# Port_Deployable_Headers.net
KiCad netlist of a schematic drawn in Altium Designer
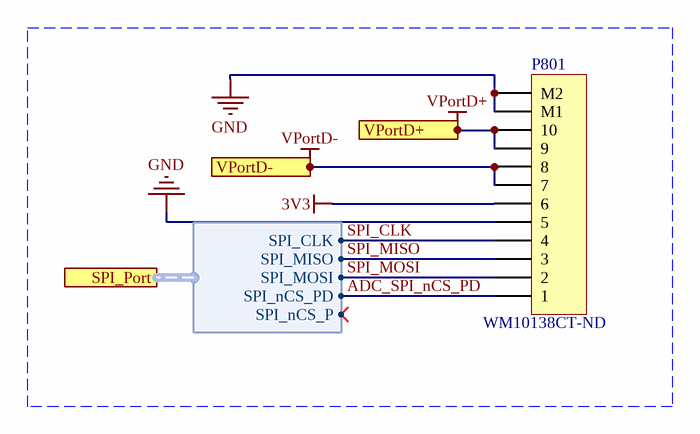
[diagram p0: Port_Deployable_Headers.SchDoc]

(export (version "E")
  (design (tool "Eeschema 10.0.6"))
  (components
    (comp (ref "P801")
      (value "WM10138CT-ND")
      (footprint "MOLX-5040501091")
      (description "CONN HEADER SMD R/A 10POS 1.5MM")
      (fields
        (field (name "PART NUMBER") "69")
        (field (name "MANUFACTURER PART NUMBER") "5040501091")
        (field (name "PUBLISHER") "Altium Limited")
      )
      (libsource (lib "Database") (part "Header 12"))
    )
  )
  (nets
    (net (code "2") (name "/ADC_SPI_nCS_PD") (class "Default")
      (node (ref "P801") (pin "1") (pinfunction "1_1") (pintype "passive"))
    )
    (net (code "3") (name "/SPI_CLK") (class "Default")
      (node (ref "P801") (pin "4") (pinfunction "4_4") (pintype "passive"))
    )
    (net (code "4") (name "/SPI_MISO") (class "Default")
      (node (ref "P801") (pin "3") (pinfunction "3_3") (pintype "passive"))
    )
    (net (code "5") (name "/SPI_MOSI") (class "Default")
      (node (ref "P801") (pin "2") (pinfunction "2_2") (pintype "passive"))
    )
    (net (code "7") (name "3V3") (class "Default")
      (node (ref "P801") (pin "6") (pinfunction "6_6") (pintype "passive"))
    )
    (net (code "8") (name "GND") (class "Default")
      (node (ref "P801") (pin "5") (pinfunction "5_5") (pintype "passive"))
      (node (ref "P801") (pin "M1") (pinfunction "M1_M1") (pintype "passive"))
      (node (ref "P801") (pin "M2") (pinfunction "M2_M2") (pintype "passive"))
    )
    (net (code "9") (name "VPortD+") (class "Default")
      (node (ref "P801") (pin "10") (pinfunction "10_10") (pintype "passive"))
      (node (ref "P801") (pin "9") (pinfunction "9_9") (pintype "passive"))
    )
    (net (code "10") (name "VPortD-") (class "Default")
      (node (ref "P801") (pin "7") (pinfunction "7_7") (pintype "passive"))
      (node (ref "P801") (pin "8") (pinfunction "8_8") (pintype "passive"))
    )
  )
)
